# HandHeld_Terminal.net
KiCad netlist of a schematic drawn in Altium Designer
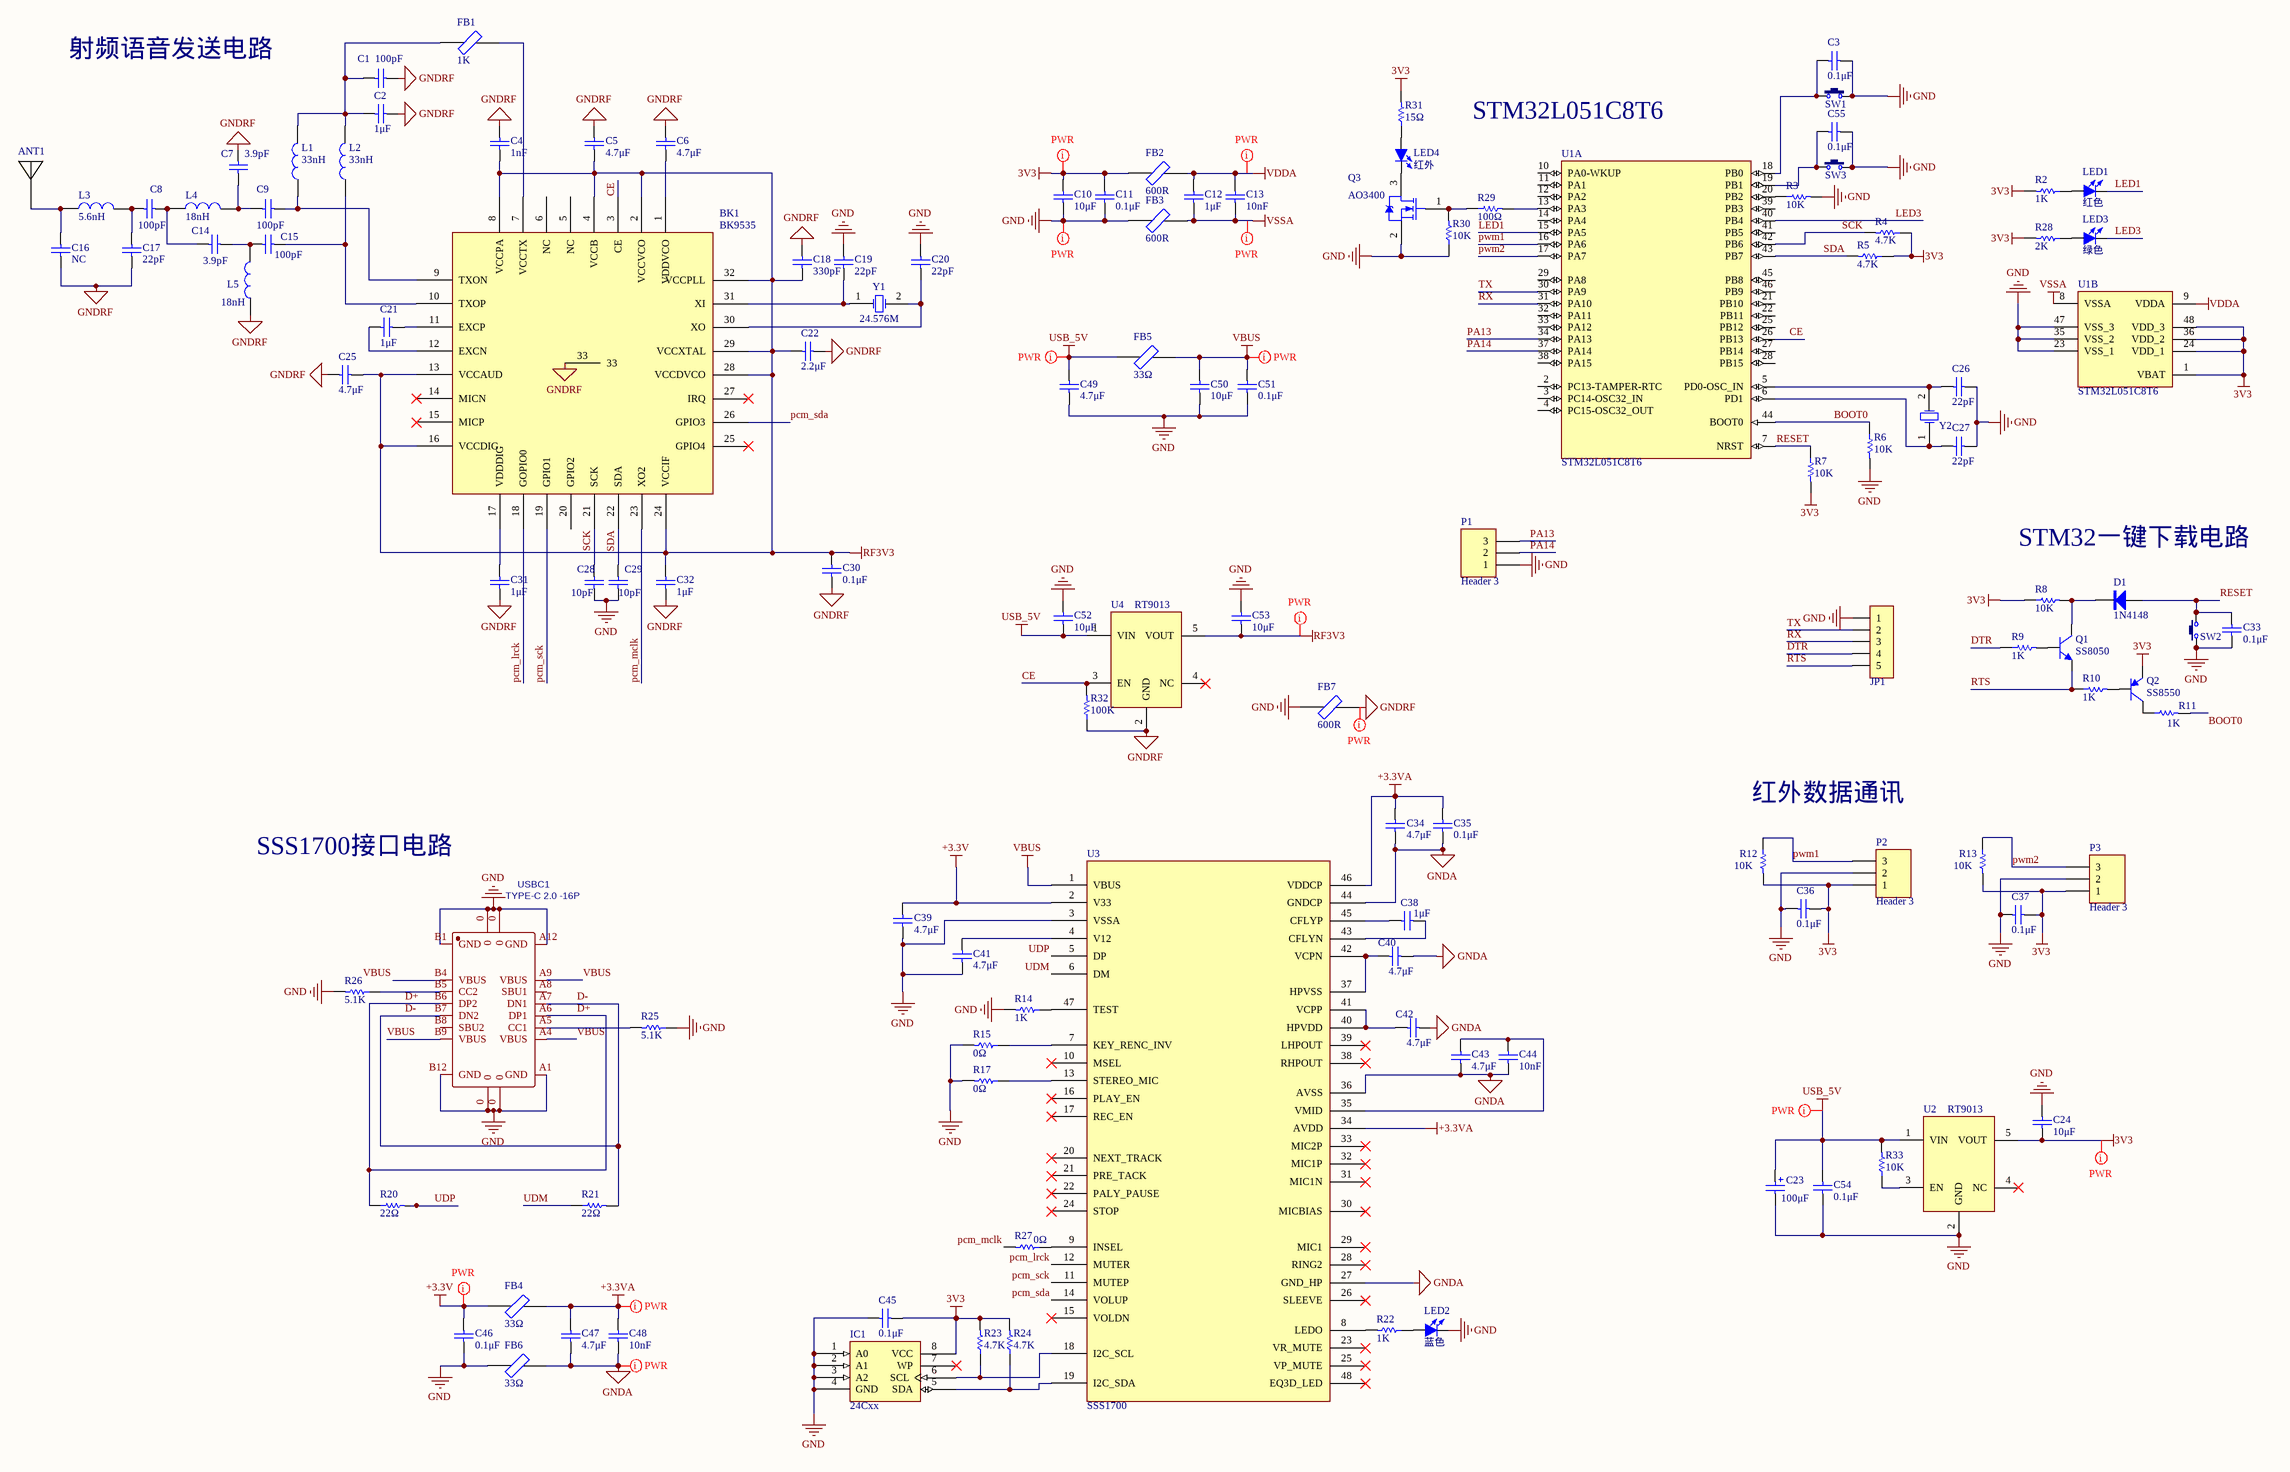
[diagram p0: HandHeld_Terminal.SchDoc]

(export (version "E")
  (design (tool "Eeschema 10.0.6"))
  (components
    (comp (ref "ANT1")
      (value "~")
      (footprint "ANT")
      (description "PCB板载天线")
      (fields (field (name "版权归属") "源创客"))
      (libsource (lib "手持发射端") (part "ANT1"))
    )
    (comp (ref "BK1") (value "BK9535") (footprint "QFN32 5x5_N") (libsource (lib "Nixie") (part "BK9530")))
    (comp (ref "C1")
      (value "100pF")
      (footprint "C 0603_L")
      (description "Capacitor")
      (fields (field (name "Comment") "Cap") (field (name "PUBLISHER") "Altium Limited"))
      (libsource (lib "Nixie") (part "Cap"))
    )
    (comp (ref "C2")
      (value "1μF")
      (footprint "C 0603_L")
      (description "Capacitor")
      (fields (field (name "Comment") "Cap") (field (name "PUBLISHER") "Altium Limited"))
      (libsource (lib "Nixie") (part "Cap"))
    )
    (comp (ref "C3")
      (value "0.1μF")
      (footprint "C 0603_L")
      (description "Capacitor")
      (fields (field (name "Comment") "Cap") (field (name "PUBLISHER") "Altium Limited"))
      (libsource (lib "Nixie") (part "Cap"))
    )
    (comp (ref "C4")
      (value "1nF")
      (footprint "C 0805_L")
      (description "Capacitor")
      (fields (field (name "Comment") "Cap") (field (name "PUBLISHER") "Altium Limited"))
      (libsource (lib "Nixie") (part "Cap"))
    )
    (comp (ref "C5")
      (value "4.7μF")
      (footprint "C 0805_L")
      (description "Capacitor")
      (fields (field (name "Comment") "Cap") (field (name "PUBLISHER") "Altium Limited"))
      (libsource (lib "Nixie") (part "Cap"))
    )
    (comp (ref "C6")
      (value "4.7μF")
      (footprint "C 0805_L")
      (description "Capacitor")
      (fields (field (name "Comment") "Cap") (field (name "PUBLISHER") "Altium Limited"))
      (libsource (lib "Nixie") (part "Cap"))
    )
    (comp (ref "C7")
      (value "3.9pF")
      (footprint "C 0603_L")
      (description "Capacitor")
      (fields (field (name "Comment") "Cap") (field (name "PUBLISHER") "Altium Limited"))
      (libsource (lib "Nixie") (part "Cap"))
    )
    (comp (ref "C8")
      (value "100pF")
      (footprint "C 0603_L")
      (description "Capacitor")
      (fields (field (name "Comment") "Cap") (field (name "PUBLISHER") "Altium Limited"))
      (libsource (lib "Nixie") (part "Cap"))
    )
    (comp (ref "C9")
      (value "100pF")
      (footprint "C 0603_L")
      (description "Capacitor")
      (fields (field (name "Comment") "Cap") (field (name "PUBLISHER") "Altium Limited"))
      (libsource (lib "Nixie") (part "Cap"))
    )
    (comp (ref "C10")
      (value "10μF")
      (footprint "C 0805_L")
      (description "Capacitor")
      (fields (field (name "Comment") "Cap") (field (name "PUBLISHER") "Altium Limited"))
      (libsource (lib "Nixie") (part "Cap"))
    )
    (comp (ref "C11")
      (value "0.1μF")
      (footprint "C 0603_L")
      (description "Capacitor")
      (fields (field (name "Comment") "Cap") (field (name "PUBLISHER") "Altium Limited"))
      (libsource (lib "Nixie") (part "Cap"))
    )
    (comp (ref "C12")
      (value "1μF")
      (footprint "C 0805_L")
      (description "Capacitor")
      (fields (field (name "Comment") "Cap") (field (name "PUBLISHER") "Altium Limited"))
      (libsource (lib "Nixie") (part "Cap"))
    )
    (comp (ref "C13")
      (value "10nF")
      (footprint "C 0805_L")
      (description "Capacitor")
      (fields (field (name "Comment") "Cap") (field (name "PUBLISHER") "Altium Limited"))
      (libsource (lib "Nixie") (part "Cap"))
    )
    (comp (ref "C14")
      (value "3.9pF")
      (footprint "C 0603_L")
      (description "Capacitor")
      (fields (field (name "Comment") "Cap") (field (name "PUBLISHER") "Altium Limited"))
      (libsource (lib "Nixie") (part "Cap"))
    )
    (comp (ref "C15")
      (value "100pF")
      (footprint "C 0603_L")
      (description "Capacitor")
      (fields (field (name "Comment") "Cap") (field (name "PUBLISHER") "Altium Limited"))
      (libsource (lib "Nixie") (part "Cap"))
    )
    (comp (ref "C16")
      (value "NC")
      (footprint "C 0603_L")
      (description "Capacitor")
      (fields (field (name "Comment") "Cap") (field (name "PUBLISHER") "Altium Limited"))
      (libsource (lib "Nixie") (part "Cap"))
    )
    (comp (ref "C17")
      (value "22pF")
      (footprint "C 0603_L")
      (description "Capacitor")
      (fields (field (name "Comment") "Cap") (field (name "PUBLISHER") "Altium Limited"))
      (libsource (lib "Nixie") (part "Cap"))
    )
    (comp (ref "C18")
      (value "330pF")
      (footprint "C 0805_L")
      (description "Capacitor")
      (fields (field (name "Comment") "Cap") (field (name "PUBLISHER") "Altium Limited"))
      (libsource (lib "Nixie") (part "Cap"))
    )
    (comp (ref "C19")
      (value "22pF")
      (footprint "C 0603_L")
      (description "Capacitor")
      (fields (field (name "Comment") "Cap") (field (name "PUBLISHER") "Altium Limited"))
      (libsource (lib "Nixie") (part "Cap"))
    )
    (comp (ref "C20")
      (value "22pF")
      (footprint "C 0603_L")
      (description "Capacitor")
      (fields (field (name "Comment") "Cap") (field (name "PUBLISHER") "Altium Limited"))
      (libsource (lib "Nixie") (part "Cap"))
    )
    (comp (ref "C21")
      (value "1μF")
      (footprint "C 0603_L")
      (description "Capacitor")
      (fields (field (name "Comment") "Cap") (field (name "PUBLISHER") "Altium Limited"))
      (libsource (lib "Nixie") (part "Cap"))
    )
    (comp (ref "C22")
      (value "2.2μF")
      (footprint "C 0805_L")
      (description "Capacitor")
      (fields (field (name "Comment") "Cap") (field (name "PUBLISHER") "Altium Limited"))
      (libsource (lib "Nixie") (part "Cap"))
    )
    (comp (ref "C23")
      (value "100μF")
      (footprint "CM C(5*5.4)")
      (description "Polarized Capacitor (Radial)")
      (fields (field (name "Comment") "Cap Pol1") (field (name "PUBLISHER") "Altium Limited"))
      (libsource (lib "Nixie") (part "Cap Pol1"))
    )
    (comp (ref "C24")
      (value "10μF")
      (footprint "C 0805_L")
      (description "Capacitor")
      (fields (field (name "Comment") "Cap") (field (name "PUBLISHER") "Altium Limited"))
      (libsource (lib "Nixie") (part "Cap"))
    )
    (comp (ref "C25")
      (value "4.7μF")
      (footprint "C 0805_L")
      (description "Capacitor")
      (fields (field (name "Comment") "Cap") (field (name "PUBLISHER") "Altium Limited"))
      (libsource (lib "Nixie") (part "Cap"))
    )
    (comp (ref "C26")
      (value "22pF")
      (footprint "C 0603_L")
      (description "Capacitor")
      (fields (field (name "Comment") "Cap") (field (name "PUBLISHER") "Altium Limited"))
      (libsource (lib "Nixie") (part "Cap"))
    )
    (comp (ref "C27")
      (value "22pF")
      (footprint "C 0603_L")
      (description "Capacitor")
      (fields (field (name "Comment") "Cap") (field (name "PUBLISHER") "Altium Limited"))
      (libsource (lib "Nixie") (part "Cap"))
    )
    (comp (ref "C28")
      (value "10pF")
      (footprint "C 0603_L")
      (description "Capacitor")
      (fields (field (name "Comment") "Cap") (field (name "PUBLISHER") "Altium Limited"))
      (libsource (lib "Nixie") (part "Cap"))
    )
    (comp (ref "C29")
      (value "10pF")
      (footprint "C 0603_L")
      (description "Capacitor")
      (fields (field (name "Comment") "Cap") (field (name "PUBLISHER") "Altium Limited"))
      (libsource (lib "Nixie") (part "Cap"))
    )
    (comp (ref "C30")
      (value "0.1μF")
      (footprint "C 0603_L")
      (description "Capacitor")
      (fields (field (name "Comment") "Cap") (field (name "PUBLISHER") "Altium Limited"))
      (libsource (lib "Nixie") (part "Cap"))
    )
    (comp (ref "C31")
      (value "1μF")
      (footprint "C 0805_L")
      (description "Capacitor")
      (fields (field (name "Comment") "Cap") (field (name "PUBLISHER") "Altium Limited"))
      (libsource (lib "Nixie") (part "Cap"))
    )
    (comp (ref "C32")
      (value "1μF")
      (footprint "C 0805_L")
      (description "Capacitor")
      (fields (field (name "Comment") "Cap") (field (name "PUBLISHER") "Altium Limited"))
      (libsource (lib "Nixie") (part "Cap"))
    )
    (comp (ref "C33")
      (value "0.1μF")
      (footprint "C 0603_L")
      (description "Capacitor")
      (fields (field (name "Comment") "Cap") (field (name "PUBLISHER") "Altium Limited"))
      (libsource (lib "Nixie") (part "Cap"))
    )
    (comp (ref "C34")
      (value "4.7μF")
      (footprint "C 0805_L")
      (description "Capacitor")
      (fields (field (name "Comment") "Cap") (field (name "PUBLISHER") "Altium Limited"))
      (libsource (lib "Nixie") (part "Cap"))
    )
    (comp (ref "C35")
      (value "0.1μF")
      (footprint "C 0603_L")
      (description "Capacitor")
      (fields (field (name "Comment") "Cap") (field (name "PUBLISHER") "Altium Limited"))
      (libsource (lib "Nixie") (part "Cap"))
    )
    (comp (ref "C36")
      (value "0.1μF")
      (footprint "C 0603_L")
      (description "Capacitor")
      (fields (field (name "Comment") "Cap") (field (name "PUBLISHER") "Altium Limited"))
      (libsource (lib "Nixie") (part "Cap"))
    )
    (comp (ref "C37")
      (value "0.1μF")
      (footprint "C 0603_L")
      (description "Capacitor")
      (fields (field (name "Comment") "Cap") (field (name "PUBLISHER") "Altium Limited"))
      (libsource (lib "Nixie") (part "Cap"))
    )
    (comp (ref "C38")
      (value "1μF")
      (footprint "C 0805_L")
      (description "Capacitor")
      (fields (field (name "Comment") "Cap") (field (name "PUBLISHER") "Altium Limited"))
      (libsource (lib "Nixie") (part "Cap"))
    )
    (comp (ref "C39")
      (value "4.7μF")
      (footprint "C 0805_L")
      (description "Capacitor")
      (fields (field (name "Comment") "Cap") (field (name "PUBLISHER") "Altium Limited"))
      (libsource (lib "Nixie") (part "Cap"))
    )
    (comp (ref "C40")
      (value "4.7μF")
      (footprint "C 0805_L")
      (description "Capacitor")
      (fields (field (name "Comment") "Cap") (field (name "PUBLISHER") "Altium Limited"))
      (libsource (lib "Nixie") (part "Cap"))
    )
    (comp (ref "C41")
      (value "4.7μF")
      (footprint "C 0805_L")
      (description "Capacitor")
      (fields (field (name "Comment") "Cap") (field (name "PUBLISHER") "Altium Limited"))
      (libsource (lib "Nixie") (part "Cap"))
    )
    (comp (ref "C42")
      (value "4.7μF")
      (footprint "C 0805_L")
      (description "Capacitor")
      (fields (field (name "Comment") "Cap") (field (name "PUBLISHER") "Altium Limited"))
      (libsource (lib "Nixie") (part "Cap"))
    )
    (comp (ref "C43")
      (value "4.7μF")
      (footprint "C 0805_L")
      (description "Capacitor")
      (fields (field (name "Comment") "Cap") (field (name "PUBLISHER") "Altium Limited"))
      (libsource (lib "Nixie") (part "Cap"))
    )
    (comp (ref "C44")
      (value "10nF")
      (footprint "C 0805_L")
      (description "Capacitor")
      (fields (field (name "Comment") "Cap") (field (name "PUBLISHER") "Altium Limited"))
      (libsource (lib "Nixie") (part "Cap"))
    )
    (comp (ref "C45")
      (value "0.1μF")
      (footprint "C 0603_L")
      (description "Capacitor")
      (fields (field (name "Comment") "Cap") (field (name "PUBLISHER") "Altium Limited"))
      (libsource (lib "Nixie") (part "Cap"))
    )
    (comp (ref "C46")
      (value "0.1μF")
      (footprint "C 0603_L")
      (description "Capacitor")
      (fields (field (name "Comment") "Cap") (field (name "PUBLISHER") "Altium Limited"))
      (libsource (lib "Nixie") (part "Cap"))
    )
    (comp (ref "C47")
      (value "4.7μF")
      (footprint "C 0805_L")
      (description "Capacitor")
      (fields (field (name "Comment") "Cap") (field (name "PUBLISHER") "Altium Limited"))
      (libsource (lib "Nixie") (part "Cap"))
    )
    (comp (ref "C48")
      (value "10nF")
      (footprint "C 0805_L")
      (description "Capacitor")
      (fields (field (name "Comment") "Cap") (field (name "PUBLISHER") "Altium Limited"))
      (libsource (lib "Nixie") (part "Cap"))
    )
    (comp (ref "C49")
      (value "4.7μF")
      (footprint "C 0805_L")
      (description "Capacitor")
      (fields (field (name "Comment") "Cap") (field (name "PUBLISHER") "Altium Limited"))
      (libsource (lib "Nixie") (part "Cap"))
    )
    (comp (ref "C50")
      (value "10μF")
      (footprint "C 0805_L")
      (description "Capacitor")
      (fields (field (name "Comment") "Cap") (field (name "PUBLISHER") "Altium Limited"))
      (libsource (lib "Nixie") (part "Cap"))
    )
    (comp (ref "C51")
      (value "0.1μF")
      (footprint "C 0603_L")
      (description "Capacitor")
      (fields (field (name "Comment") "Cap") (field (name "PUBLISHER") "Altium Limited"))
      (libsource (lib "Nixie") (part "Cap"))
    )
    (comp (ref "C52")
      (value "10μF")
      (footprint "C 0805_L")
      (description "Capacitor")
      (fields (field (name "Comment") "Cap") (field (name "PUBLISHER") "Altium Limited"))
      (libsource (lib "Nixie") (part "Cap"))
    )
    (comp (ref "C53")
      (value "10μF")
      (footprint "C 0805_L")
      (description "Capacitor")
      (fields (field (name "Comment") "Cap") (field (name "PUBLISHER") "Altium Limited"))
      (libsource (lib "Nixie") (part "Cap"))
    )
    (comp (ref "C54")
      (value "0.1μF")
      (footprint "C 0603_L")
      (description "Capacitor")
      (fields (field (name "Comment") "Cap") (field (name "PUBLISHER") "Altium Limited"))
      (libsource (lib "Nixie") (part "Cap"))
    )
    (comp (ref "C55")
      (value "0.1μF")
      (footprint "C 0603_L")
      (description "Capacitor")
      (fields (field (name "Comment") "Cap") (field (name "PUBLISHER") "Altium Limited"))
      (libsource (lib "Nixie") (part "Cap"))
    )
    (comp (ref "D1")
      (value "1N4148")
      (footprint "SOD-323")
      (description "开关二极管")
      (libsource (lib "Nixie") (part "1N4148"))
    )
    (comp (ref "FB1")
      (value "1K")
      (footprint "C 0603_L")
      (description "铁氧体磁珠")
      (fields (field (name "Comment") "Ferrite bead"))
      (libsource (lib "Nixie") (part "Ferrite bead"))
    )
    (comp (ref "FB2")
      (value "600R")
      (footprint "C 0603_L")
      (description "铁氧体磁珠")
      (fields (field (name "Comment") "Ferrite bead"))
      (libsource (lib "Nixie") (part "Ferrite bead"))
    )
    (comp (ref "FB3")
      (value "600R")
      (footprint "C 0603_L")
      (description "铁氧体磁珠")
      (fields (field (name "Comment") "Ferrite bead"))
      (libsource (lib "Nixie") (part "Ferrite bead"))
    )
    (comp (ref "FB4")
      (value "33Ω")
      (footprint "C 0603_L")
      (description "铁氧体磁珠")
      (fields (field (name "Comment") "Ferrite bead"))
      (libsource (lib "Nixie") (part "Ferrite bead"))
    )
    (comp (ref "FB5")
      (value "33Ω")
      (footprint "C 0603_L")
      (description "铁氧体磁珠")
      (fields (field (name "Comment") "Ferrite bead"))
      (libsource (lib "Nixie") (part "Ferrite bead"))
    )
    (comp (ref "FB6")
      (value "33Ω")
      (footprint "C 0603_L")
      (description "铁氧体磁珠")
      (fields (field (name "Comment") "Ferrite bead"))
      (libsource (lib "Nixie") (part "Ferrite bead"))
    )
    (comp (ref "FB7")
      (value "600R")
      (footprint "C 0603_L")
      (description "铁氧体磁珠")
      (fields (field (name "Comment") "Ferrite bead"))
      (libsource (lib "Nixie") (part "Ferrite bead"))
    )
    (comp (ref "IC1")
      (value "24Cxx")
      (footprint "SOP8_L")
      (description "外置EEPROM")
      (fields (field (name "版权归属") "封装库来自淘宝 ID：黄晶宝石"))
      (libsource (lib "Nixie") (part "24Cxx"))
    )
    (comp (ref "JP1")
      (value "HDR-1X5")
      (footprint "HDR2.0-LI-5P")
      (description "5P接插件")
      (fields (field (name "版权归属") "封装库来自淘宝 ID：黄晶宝石"))
      (libsource (lib "Nixie") (part "Header 5"))
    )
    (comp (ref "L1")
      (value "33nH")
      (footprint "L 0603")
      (description "小功率贴片电感")
      (fields (field (name "Comment") "L"))
      (libsource (lib "Nixie") (part "L"))
    )
    (comp (ref "L2")
      (value "33nH")
      (footprint "L 0603")
      (description "小功率贴片电感")
      (fields (field (name "Comment") "L"))
      (libsource (lib "Nixie") (part "L"))
    )
    (comp (ref "L3")
      (value "5.6nH")
      (footprint "L 0603")
      (description "小功率贴片电感")
      (fields (field (name "Comment") "L"))
      (libsource (lib "Nixie") (part "L"))
    )
    (comp (ref "L4")
      (value "18nH")
      (footprint "L 0603")
      (description "小功率贴片电感")
      (fields (field (name "Comment") "L"))
      (libsource (lib "Nixie") (part "L"))
    )
    (comp (ref "L5")
      (value "18nH")
      (footprint "L 0603")
      (description "小功率贴片电感")
      (fields (field (name "Comment") "L"))
      (libsource (lib "Nixie") (part "L"))
    )
    (comp (ref "LED1")
      (value "红色")
      (footprint "LED 0805R")
      (description "贴片LED")
      (fields (field (name "版权归属") "封装库来自淘宝 ID：黄晶宝石"))
      (libsource (lib "Nixie") (part "LED-SMD"))
    )
    (comp (ref "LED2")
      (value "蓝色")
      (footprint "LED 0805B")
      (description "贴片LED")
      (fields (field (name "版权归属") "封装库来自淘宝 ID：黄晶宝石"))
      (libsource (lib "Nixie") (part "LED-SMD"))
    )
    (comp (ref "LED3")
      (value "绿色")
      (footprint "LED 0805G")
      (description "贴片LED")
      (fields (field (name "版权归属") "封装库来自淘宝 ID：黄晶宝石"))
      (libsource (lib "Nixie") (part "LED-SMD"))
    )
    (comp (ref "LED4")
      (value "红外")
      (footprint "LED 3MM-R")
      (description "贴片LED")
      (fields (field (name "版权归属") "封装库来自淘宝 ID：黄晶宝石"))
      (libsource (lib "Nixie") (part "LED-SMD"))
    )
    (comp (ref "P1")
      (value "Header 3")
      (footprint "HDR1X3")
      (description "Header, 3-Pin")
      (fields (field (name "PUBLISHER") "Altium Limited"))
      (libsource (lib "") (part "Header 3_1"))
    )
    (comp (ref "P2")
      (value "Header 3")
      (footprint "HDR1X3")
      (description "Header, 3-Pin")
      (fields (field (name "PUBLISHER") "Altium Limited"))
      (libsource (lib "Miscellaneous Connectors") (part "Header 3"))
    )
    (comp (ref "P3")
      (value "Header 3")
      (footprint "HDR1X3")
      (description "Header, 3-Pin")
      (fields (field (name "PUBLISHER") "Altium Limited"))
      (libsource (lib "Miscellaneous Connectors") (part "Header 3"))
    )
    (comp (ref "Q1")
      (value "SS8050")
      (footprint "SOT-23-3L")
      (description "高频放大-NPN型")
      (fields (field (name "版权归属") "封装库来自淘宝 ID：黄晶宝石"))
      (libsource (lib "Nixie") (part "8050-SMD"))
    )
    (comp (ref "Q2")
      (value "SS8550")
      (footprint "SOT-23-3L")
      (description "高频放大-PNP型")
      (fields (field (name "版权归属") "封装库来自淘宝 ID：黄晶宝石"))
      (libsource (lib "Nixie") (part "8550-SMD"))
    )
    (comp (ref "Q3")
      (value "AO3400")
      (footprint "SOT-23-3L")
      (description "N-Channel Power MOSFET")
      (fields (field (name "PUBLISHER") "Altium Limited"))
      (libsource (lib "Nixie") (part "NMOS-2"))
    )
    (comp (ref "R2")
      (value "1K")
      (footprint "R 0805_L")
      (description "Resistor")
      (fields (field (name "PUBLISHER") "Altium Limited"))
      (libsource (lib "Nixie") (part "Resistor"))
    )
    (comp (ref "R3")
      (value "10K")
      (footprint "R 0805_L")
      (description "Resistor")
      (fields (field (name "PUBLISHER") "Altium Limited"))
      (libsource (lib "Nixie") (part "Resistor"))
    )
    (comp (ref "R4")
      (value "4.7K")
      (footprint "R 0603_L")
      (description "Resistor")
      (fields (field (name "PUBLISHER") "Altium Limited"))
      (libsource (lib "Nixie") (part "Resistor"))
    )
    (comp (ref "R5")
      (value "4.7K")
      (footprint "R 0603_L")
      (description "Resistor")
      (fields (field (name "PUBLISHER") "Altium Limited"))
      (libsource (lib "Nixie") (part "Resistor"))
    )
    (comp (ref "R6")
      (value "10K")
      (footprint "R 0805_L")
      (description "Resistor")
      (fields (field (name "PUBLISHER") "Altium Limited"))
      (libsource (lib "Nixie") (part "Resistor"))
    )
    (comp (ref "R7")
      (value "10K")
      (footprint "R 0805_L")
      (description "Resistor")
      (fields (field (name "PUBLISHER") "Altium Limited"))
      (libsource (lib "Nixie") (part "Resistor"))
    )
    (comp (ref "R8")
      (value "10K")
      (footprint "R 0805_L")
      (description "Resistor")
      (fields (field (name "PUBLISHER") "Altium Limited"))
      (libsource (lib "Nixie") (part "Resistor"))
    )
    (comp (ref "R9")
      (value "1K")
      (footprint "R 0805_L")
      (description "Resistor")
      (fields (field (name "PUBLISHER") "Altium Limited"))
      (libsource (lib "Nixie") (part "Resistor"))
    )
    (comp (ref "R10")
      (value "1K")
      (footprint "R 0805_L")
      (description "Resistor")
      (fields (field (name "PUBLISHER") "Altium Limited"))
      (libsource (lib "Nixie") (part "Resistor"))
    )
    (comp (ref "R11")
      (value "1K")
      (footprint "R 0805_L")
      (description "Resistor")
      (fields (field (name "PUBLISHER") "Altium Limited"))
      (libsource (lib "Nixie") (part "Resistor"))
    )
    (comp (ref "R12")
      (value "10K")
      (footprint "R 0805_L")
      (description "Resistor")
      (fields (field (name "PUBLISHER") "Altium Limited"))
      (libsource (lib "Nixie") (part "Resistor"))
    )
    (comp (ref "R13")
      (value "10K")
      (footprint "R 0805_L")
      (description "Resistor")
      (fields (field (name "PUBLISHER") "Altium Limited"))
      (libsource (lib "Nixie") (part "Resistor"))
    )
    (comp (ref "R14")
      (value "1K")
      (footprint "R 0805_L")
      (description "Resistor")
      (fields (field (name "PUBLISHER") "Altium Limited"))
      (libsource (lib "Nixie") (part "Resistor"))
    )
    (comp (ref "R15")
      (value "0Ω")
      (footprint "R 0603_L")
      (description "Resistor")
      (fields (field (name "PUBLISHER") "Altium Limited"))
      (libsource (lib "Nixie") (part "Resistor"))
    )
    (comp (ref "R17")
      (value "0Ω")
      (footprint "R 0603_L")
      (description "Resistor")
      (fields (field (name "PUBLISHER") "Altium Limited"))
      (libsource (lib "Nixie") (part "Resistor"))
    )
    (comp (ref "R20")
      (value "22Ω")
      (footprint "R 0603_L")
      (description "Resistor")
      (fields (field (name "PUBLISHER") "Altium Limited"))
      (libsource (lib "Nixie") (part "Resistor"))
    )
    (comp (ref "R21")
      (value "22Ω")
      (footprint "R 0603_L")
      (description "Resistor")
      (fields (field (name "PUBLISHER") "Altium Limited"))
      (libsource (lib "Nixie") (part "Resistor"))
    )
    (comp (ref "R22")
      (value "1K")
      (footprint "R 0805_L")
      (description "Resistor")
      (fields (field (name "PUBLISHER") "Altium Limited"))
      (libsource (lib "Nixie") (part "Resistor"))
    )
    (comp (ref "R23")
      (value "4.7K")
      (footprint "R 0603_L")
      (description "Resistor")
      (fields (field (name "PUBLISHER") "Altium Limited"))
      (libsource (lib "Nixie") (part "Resistor"))
    )
    (comp (ref "R24")
      (value "4.7K")
      (footprint "R 0603_L")
      (description "Resistor")
      (fields (field (name "PUBLISHER") "Altium Limited"))
      (libsource (lib "Nixie") (part "Resistor"))
    )
    (comp (ref "R25")
      (value "5.1K")
      (footprint "R 0603_L")
      (description "Resistor")
      (fields (field (name "PUBLISHER") "Altium Limited"))
      (libsource (lib "Nixie") (part "Resistor"))
    )
    (comp (ref "R26")
      (value "5.1K")
      (footprint "R 0603_L")
      (description "Resistor")
      (fields (field (name "PUBLISHER") "Altium Limited"))
      (libsource (lib "Nixie") (part "Resistor"))
    )
    (comp (ref "R27")
      (value "0Ω")
      (footprint "R 0603_L")
      (description "Resistor")
      (fields (field (name "PUBLISHER") "Altium Limited"))
      (libsource (lib "Nixie") (part "Resistor"))
    )
    (comp (ref "R28")
      (value "2K")
      (footprint "R 0805_L")
      (description "Resistor")
      (fields (field (name "PUBLISHER") "Altium Limited"))
      (libsource (lib "Nixie") (part "Resistor"))
    )
    (comp (ref "R29")
      (value "100Ω")
      (footprint "R 0805_L")
      (description "Resistor")
      (fields (field (name "PUBLISHER") "Altium Limited"))
      (libsource (lib "Nixie") (part "Resistor"))
    )
    (comp (ref "R30")
      (value "10K")
      (footprint "R 0805_L")
      (description "Resistor")
      (fields (field (name "PUBLISHER") "Altium Limited"))
      (libsource (lib "Nixie") (part "Resistor"))
    )
    (comp (ref "R31")
      (value "15Ω")
      (footprint "R 1206_L")
      (description "Resistor")
      (fields (field (name "PUBLISHER") "Altium Limited"))
      (libsource (lib "Nixie") (part "Resistor"))
    )
    (comp (ref "R32")
      (value "100K")
      (footprint "R 0805_L")
      (description "Resistor")
      (fields (field (name "PUBLISHER") "Altium Limited"))
      (libsource (lib "Nixie") (part "Resistor"))
    )
    (comp (ref "R33")
      (value "10K")
      (footprint "R 0805_L")
      (description "Resistor")
      (fields (field (name "PUBLISHER") "Altium Limited"))
      (libsource (lib "Nixie") (part "Resistor"))
    )
    (comp (ref "SW1")
      (value "3x6x5")
      (footprint "TSW SMD-3*6*2.5")
      (description "3x6轻触开关")
      (fields (field (name "版权归属") "封装库来自淘宝 ID：黄晶宝石"))
      (libsource (lib "Nixie") (part "TSW 3x6"))
    )
    (comp (ref "SW2")
      (value "3x6x5")
      (footprint "TSW SMD-3*6*2.5")
      (description "3x6轻触开关")
      (fields (field (name "版权归属") "封装库来自淘宝 ID：黄晶宝石"))
      (libsource (lib "") (part "TSW 3x6_1"))
    )
    (comp (ref "SW3")
      (value "3x6x5")
      (footprint "TSW SMD-3*6*2.5")
      (description "3x6轻触开关")
      (fields (field (name "版权归属") "封装库来自淘宝 ID：黄晶宝石"))
      (libsource (lib "Nixie") (part "TSW 3x6"))
    )
    (comp (ref "U1")
      (value "STM32L051C8T6")
      (footprint "LQFP48_L")
      (description "ARM")
      (libsource (lib "") (part "STM32F103C8T6_1"))
    )
    (comp (ref "U2")
      (value "RT9013")
      (footprint "SOT23-5L")
      (description "LDO")
      (libsource (lib "HandHeld_terminal") (part "RT9013"))
    )
    (comp (ref "U3")
      (value "SSS1700")
      (footprint "LQFP48_L")
      (description "USB音频芯片")
      (libsource (lib "Nixie") (part "SSS1700"))
    )
    (comp (ref "U4")
      (value "RT9013")
      (footprint "SOT23-5L")
      (description "LDO")
      (libsource (lib "HandHeld_terminal") (part "RT9013"))
    )
    (comp (ref "USBC1")
      (value "TYPE-C 2.0 -16P")
      (footprint "USB-C-SMD_TYPE-C-USB-5")
      (description "USB2.0 Type-C 母座 16Pin")
      (libsource (lib "Nixie") (part "USB2.0 Type-C 16Pin母座"))
    )
    (comp (ref "Y1")
      (value "24.576M")
      (footprint "OSC 5032-2P")
      (description "Crystal Oscillator")
      (fields (field (name "PUBLISHER") "Altium Limited"))
      (libsource (lib "Miscellaneous Devices") (part "XTAL"))
    )
    (comp (ref "Y2")
      (value "8MHz ±20ppm 20pF")
      (footprint "OSC 5032-2P")
      (description "贴片晶振")
      (libsource (lib "HandHeld_terminal") (part "SMD-5032_2P 8MHz 20ppm 20pF"))
    )
  )
  (nets
    (net (code "1") (name "+3.3V") (class "Default")
      (node (ref "C39") (pin "2") (pinfunction "2_2") (pintype "passive"))
      (node (ref "C46") (pin "2") (pinfunction "2_2") (pintype "passive"))
      (node (ref "FB4") (pin "1") (pinfunction "1_1") (pintype "passive"))
      (node (ref "U3") (pin "2") (pinfunction "V33_2") (pintype "passive"))
    )
    (net (code "2") (name "+3.3VA") (class "Default")
      (node (ref "C34") (pin "2") (pinfunction "2_2") (pintype "passive"))
      (node (ref "C35") (pin "2") (pinfunction "2_2") (pintype "passive"))
      (node (ref "C47") (pin "2") (pinfunction "2_2") (pintype "passive"))
      (node (ref "C48") (pin "2") (pinfunction "2_2") (pintype "passive"))
      (node (ref "FB4") (pin "2") (pinfunction "2_2") (pintype "passive"))
      (node (ref "U3") (pin "34") (pinfunction "AVDD_34") (pintype "passive"))
      (node (ref "U3") (pin "46") (pinfunction "VDDCP_46") (pintype "passive"))
    )
    (net (code "3") (name "/BOOT0") (class "Default")
      (node (ref "R11") (pin "2") (pinfunction "2_2") (pintype "passive"))
      (node (ref "R6") (pin "1") (pinfunction "1_1") (pintype "passive"))
      (node (ref "U1") (pin "44") (pinfunction "BOOT0_44") (pintype "input"))
    )
    (net (code "4") (name "/CE") (class "Default")
      (node (ref "BK1") (pin "3") (pinfunction "CE_3") (pintype "passive"))
      (node (ref "R32") (pin "2") (pinfunction "2_2") (pintype "passive"))
      (node (ref "U1") (pin "26") (pinfunction "PB13_26") (pintype "bidirectional"))
      (node (ref "U4") (pin "3") (pinfunction "EN_3") (pintype "passive"))
    )
    (net (code "5") (name "/D+") (class "Default")
      (node (ref "R20") (pin "1") (pinfunction "1_1") (pintype "passive"))
      (node (ref "USBC1") (pin "A6") (pinfunction "DP1_A6") (pintype "passive"))
      (node (ref "USBC1") (pin "B6") (pinfunction "DP2_B6") (pintype "passive"))
    )
    (net (code "6") (name "/D-") (class "Default")
      (node (ref "R21") (pin "2") (pinfunction "2_2") (pintype "passive"))
      (node (ref "USBC1") (pin "A7") (pinfunction "DN1_A7") (pintype "passive"))
      (node (ref "USBC1") (pin "B7") (pinfunction "DN2_B7") (pintype "passive"))
    )
    (net (code "7") (name "/DTR") (class "Default")
      (node (ref "JP1") (pin "4") (pinfunction "4_4") (pintype "passive"))
      (node (ref "R9") (pin "1") (pinfunction "1_1") (pintype "passive"))
    )
    (net (code "8") (name "/LED1") (class "Default")
      (node (ref "LED1") (pin "2") (pinfunction "K_2") (pintype "passive"))
      (node (ref "U1") (pin "15") (pinfunction "PA5_15") (pintype "bidirectional"))
    )
    (net (code "9") (name "/LED3") (class "Default")
      (node (ref "LED3") (pin "2") (pinfunction "K_2") (pintype "passive"))
      (node (ref "U1") (pin "40") (pinfunction "PB4_40") (pintype "bidirectional"))
    )
    (net (code "10") (name "/PA13") (class "Default")
      (node (ref "P1") (pin "3") (pinfunction "3_3") (pintype "passive"))
      (node (ref "U1") (pin "34") (pinfunction "PA13_34") (pintype "bidirectional"))
    )
    (net (code "11") (name "/PA14") (class "Default")
      (node (ref "P1") (pin "2") (pinfunction "2_2") (pintype "passive"))
      (node (ref "U1") (pin "37") (pinfunction "PA14_37") (pintype "bidirectional"))
    )
    (net (code "12") (name "/RESET") (class "Default")
      (node (ref "C33") (pin "2") (pinfunction "2_2") (pintype "passive"))
      (node (ref "D1") (pin "1") (pinfunction "A_1") (pintype "passive"))
      (node (ref "R7") (pin "1") (pinfunction "1_1") (pintype "passive"))
      (node (ref "SW2") (pin "2") (pinfunction "2_2") (pintype "passive"))
      (node (ref "U1") (pin "7") (pinfunction "NRST_7") (pintype "bidirectional"))
    )
    (net (code "13") (name "/RTS") (class "Default")
      (node (ref "JP1") (pin "5") (pinfunction "5_5") (pintype "passive"))
      (node (ref "Q1") (pin "2") (pinfunction "E_2") (pintype "passive"))
      (node (ref "R10") (pin "1") (pinfunction "1_1") (pintype "passive"))
    )
    (net (code "14") (name "/RX") (class "Default")
      (node (ref "JP1") (pin "3") (pinfunction "3_3") (pintype "passive"))
      (node (ref "U1") (pin "31") (pinfunction "PA10_31") (pintype "bidirectional"))
    )
    (net (code "15") (name "/SCK") (class "Default")
      (node (ref "BK1") (pin "21") (pinfunction "SCK_21") (pintype "passive"))
      (node (ref "C28") (pin "2") (pinfunction "2_2") (pintype "passive"))
      (node (ref "R4") (pin "2") (pinfunction "2_2") (pintype "passive"))
      (node (ref "U1") (pin "42") (pinfunction "PB6_42") (pintype "bidirectional"))
    )
    (net (code "16") (name "/SDA") (class "Default")
      (node (ref "BK1") (pin "22") (pinfunction "SDA_22") (pintype "passive"))
      (node (ref "C29") (pin "2") (pinfunction "2_2") (pintype "passive"))
      (node (ref "R5") (pin "2") (pinfunction "2_2") (pintype "passive"))
      (node (ref "U1") (pin "43") (pinfunction "PB7_43") (pintype "bidirectional"))
    )
    (net (code "17") (name "/TX") (class "Default")
      (node (ref "JP1") (pin "2") (pinfunction "2_2") (pintype "passive"))
      (node (ref "U1") (pin "30") (pinfunction "PA9_30") (pintype "bidirectional"))
    )
    (net (code "18") (name "/UDM") (class "Default")
      (node (ref "R21") (pin "1") (pinfunction "1_1") (pintype "passive"))
      (node (ref "U3") (pin "6") (pinfunction "DM_6") (pintype "passive"))
    )
    (net (code "19") (name "/UDP") (class "Default")
      (node (ref "R20") (pin "2") (pinfunction "2_2") (pintype "passive"))
      (node (ref "U3") (pin "5") (pinfunction "DP_5") (pintype "passive"))
    )
    (net (code "20") (name "/pcm_lrck") (class "Default")
      (node (ref "BK1") (pin "18") (pinfunction "GOPIO0_18") (pintype "passive"))
      (node (ref "U3") (pin "12") (pinfunction "MUTER_12") (pintype "passive"))
    )
    (net (code "21") (name "/pcm_mclk") (class "Default")
      (node (ref "BK1") (pin "23") (pinfunction "XO2_23") (pintype "passive"))
      (node (ref "R27") (pin "2") (pinfunction "2_2") (pintype "passive"))
    )
    (net (code "22") (name "/pcm_sck") (class "Default")
      (node (ref "BK1") (pin "19") (pinfunction "GPIO1_19") (pintype "passive"))
      (node (ref "U3") (pin "11") (pinfunction "MUTEP_11") (pintype "passive"))
    )
    (net (code "23") (name "/pcm_sda") (class "Default")
      (node (ref "BK1") (pin "26") (pinfunction "GPIO3_26") (pintype "passive"))
      (node (ref "U3") (pin "14") (pinfunction "VOLUP_14") (pintype "passive"))
    )
    (net (code "24") (name "/pwm1") (class "Default")
      (node (ref "P2") (pin "3") (pinfunction "3_3") (pintype "passive"))
      (node (ref "R12") (pin "1") (pinfunction "1_1") (pintype "passive"))
      (node (ref "U1") (pin "16") (pinfunction "PA6_16") (pintype "bidirectional"))
    )
    (net (code "25") (name "/pwm2") (class "Default")
      (node (ref "P3") (pin "3") (pinfunction "3_3") (pintype "passive"))
      (node (ref "R13") (pin "1") (pinfunction "1_1") (pintype "passive"))
      (node (ref "U1") (pin "17") (pinfunction "PA7_17") (pintype "bidirectional"))
    )
    (net (code "26") (name "3V3") (class "Default")
      (node (ref "C10") (pin "2") (pinfunction "2_2") (pintype "passive"))
      (node (ref "C11") (pin "2") (pinfunction "2_2") (pintype "passive"))
      (node (ref "C24") (pin "1") (pinfunction "1_1") (pintype "passive"))
      (node (ref "C36") (pin "1") (pinfunction "1_1") (pintype "passive"))
      (node (ref "C37") (pin "1") (pinfunction "1_1") (pintype "passive"))
      (node (ref "C45") (pin "1") (pinfunction "1_1") (pintype "passive"))
      (node (ref "FB2") (pin "1") (pinfunction "1_1") (pintype "passive"))
      (node (ref "IC1") (pin "8") (pinfunction "VCC_8") (pintype "power_in"))
      (node (ref "P2") (pin "1") (pinfunction "1_1") (pintype "passive"))
      (node (ref "P3") (pin "1") (pinfunction "1_1") (pintype "passive"))
      (node (ref "Q2") (pin "2") (pinfunction "E_2") (pintype "passive"))
      (node (ref "R12") (pin "2") (pinfunction "2_2") (pintype "passive"))
      (node (ref "R13") (pin "2") (pinfunction "2_2") (pintype "passive"))
      (node (ref "R2") (pin "2") (pinfunction "2_2") (pintype "passive"))
      (node (ref "R23") (pin "2") (pinfunction "2_2") (pintype "passive"))
      (node (ref "R24") (pin "2") (pinfunction "2_2") (pintype "passive"))
      (node (ref "R28") (pin "2") (pinfunction "2_2") (pintype "passive"))
      (node (ref "R31") (pin "2") (pinfunction "2_2") (pintype "passive"))
      (node (ref "R4") (pin "1") (pinfunction "1_1") (pintype "passive"))
      (node (ref "R5") (pin "1") (pinfunction "1_1") (pintype "passive"))
      (node (ref "R7") (pin "2") (pinfunction "2_2") (pintype "passive"))
      (node (ref "R8") (pin "1") (pinfunction "1_1") (pintype "passive"))
      (node (ref "U1") (pin "1") (pinfunction "VBAT_1") (pintype "power_in"))
      (node (ref "U1") (pin "24") (pinfunction "VDD_1_24") (pintype "power_in"))
      (node (ref "U1") (pin "36") (pinfunction "VDD_2_36") (pintype "power_in"))
      (node (ref "U1") (pin "48") (pinfunction "VDD_3_48") (pintype "power_in"))
      (node (ref "U2") (pin "5") (pinfunction "VOUT_5") (pintype "passive"))
    )
    (net (code "27") (name "GND") (class "Default")
      (node (ref "C10") (pin "1") (pinfunction "1_1") (pintype "passive"))
      (node (ref "C11") (pin "1") (pinfunction "1_1") (pintype "passive"))
      (node (ref "C19") (pin "2") (pinfunction "2_2") (pintype "passive"))
      (node (ref "C20") (pin "2") (pinfunction "2_2") (pintype "passive"))
      (node (ref "C23") (pin "2") (pinfunction "2_2") (pintype "passive"))
      (node (ref "C24") (pin "2") (pinfunction "2_2") (pintype "passive"))
      (node (ref "C26") (pin "1") (pinfunction "1_1") (pintype "passive"))
      (node (ref "C27") (pin "1") (pinfunction "1_1") (pintype "passive"))
      (node (ref "C28") (pin "1") (pinfunction "1_1") (pintype "passive"))
      (node (ref "C29") (pin "1") (pinfunction "1_1") (pintype "passive"))
      (node (ref "C3") (pin "1") (pinfunction "1_1") (pintype "passive"))
      (node (ref "C33") (pin "1") (pinfunction "1_1") (pintype "passive"))
      (node (ref "C36") (pin "2") (pinfunction "2_2") (pintype "passive"))
      (node (ref "C37") (pin "2") (pinfunction "2_2") (pintype "passive"))
      (node (ref "C39") (pin "1") (pinfunction "1_1") (pintype "passive"))
      (node (ref "C41") (pin "1") (pinfunction "1_1") (pintype "passive"))
      (node (ref "C45") (pin "2") (pinfunction "2_2") (pintype "passive"))
      (node (ref "C46") (pin "1") (pinfunction "1_1") (pintype "passive"))
      (node (ref "C49") (pin "1") (pinfunction "1_1") (pintype "passive"))
      (node (ref "C50") (pin "1") (pinfunction "1_1") (pintype "passive"))
      (node (ref "C51") (pin "1") (pinfunction "1_1") (pintype "passive"))
      (node (ref "C52") (pin "2") (pinfunction "2_2") (pintype "passive"))
      (node (ref "C53") (pin "2") (pinfunction "2_2") (pintype "passive"))
      (node (ref "C54") (pin "2") (pinfunction "2_2") (pintype "passive"))
      (node (ref "C55") (pin "1") (pinfunction "1_1") (pintype "passive"))
      (node (ref "FB3") (pin "1") (pinfunction "1_1") (pintype "passive"))
      (node (ref "FB6") (pin "1") (pinfunction "1_1") (pintype "passive"))
      (node (ref "FB7") (pin "1") (pinfunction "1_1") (pintype "passive"))
      (node (ref "IC1") (pin "1") (pinfunction "A0_1") (pintype "input"))
      (node (ref "IC1") (pin "2") (pinfunction "A1_2") (pintype "input"))
      (node (ref "IC1") (pin "3") (pinfunction "A2_3") (pintype "input"))
      (node (ref "IC1") (pin "4") (pinfunction "GND_4") (pintype "passive"))
      (node (ref "JP1") (pin "1") (pinfunction "1_1") (pintype "passive"))
      (node (ref "LED2") (pin "2") (pinfunction "K_2") (pintype "passive"))
      (node (ref "P1") (pin "1") (pinfunction "1_1") (pintype "passive"))
      (node (ref "P2") (pin "2") (pinfunction "2_2") (pintype "passive"))
      (node (ref "P3") (pin "2") (pinfunction "2_2") (pintype "passive"))
      (node (ref "Q3") (pin "2") (pinfunction "S_2") (pintype "passive"))
      (node (ref "R14") (pin "2") (pinfunction "2_2") (pintype "passive"))
      (node (ref "R15") (pin "2") (pinfunction "2_2") (pintype "passive"))
      (node (ref "R17") (pin "2") (pinfunction "2_2") (pintype "passive"))
      (node (ref "R25") (pin "1") (pinfunction "1_1") (pintype "passive"))
      (node (ref "R26") (pin "2") (pinfunction "2_2") (pintype "passive"))
      (node (ref "R3") (pin "2") (pinfunction "2_2") (pintype "passive"))
      (node (ref "R30") (pin "1") (pinfunction "1_1") (pintype "passive"))
      (node (ref "R6") (pin "2") (pinfunction "2_2") (pintype "passive"))
      (node (ref "SW1") (pin "2") (pinfunction "2_2") (pintype "passive"))
      (node (ref "SW2") (pin "1") (pinfunction "1_1") (pintype "passive"))
      (node (ref "SW3") (pin "2") (pinfunction "2_2") (pintype "passive"))
      (node (ref "U1") (pin "23") (pinfunction "VSS_1_23") (pintype "power_in"))
      (node (ref "U1") (pin "35") (pinfunction "VSS_2_35") (pintype "power_in"))
      (node (ref "U1") (pin "47") (pinfunction "VSS_3_47") (pintype "power_in"))
      (node (ref "U2") (pin "2") (pinfunction "GND_2") (pintype "passive"))
      (node (ref "U3") (pin "3") (pinfunction "VSSA_3") (pintype "passive"))
      (node (ref "USBC1") (pin "0") (pinfunction "0_0") (pintype "passive"))
      (node (ref "USBC1") (pin "A1") (pinfunction "GND_A1") (pintype "passive"))
      (node (ref "USBC1") (pin "A12") (pinfunction "GND_A12") (pintype "passive"))
      (node (ref "USBC1") (pin "B1") (pinfunction "GND_B1") (pintype "passive"))
      (node (ref "USBC1") (pin "B12") (pinfunction "GND_B12") (pintype "passive"))
    )
    (net (code "28") (name "GNDA") (class "Default")
      (node (ref "C34") (pin "1") (pinfunction "1_1") (pintype "passive"))
      (node (ref "C35") (pin "1") (pinfunction "1_1") (pintype "passive"))
      (node (ref "C40") (pin "1") (pinfunction "1_1") (pintype "passive"))
      (node (ref "C42") (pin "1") (pinfunction "1_1") (pintype "passive"))
      (node (ref "C43") (pin "1") (pinfunction "1_1") (pintype "passive"))
      (node (ref "C44") (pin "1") (pinfunction "1_1") (pintype "passive"))
      (node (ref "C47") (pin "1") (pinfunction "1_1") (pintype "passive"))
      (node (ref "C48") (pin "1") (pinfunction "1_1") (pintype "passive"))
      (node (ref "FB6") (pin "2") (pinfunction "2_2") (pintype "passive"))
      (node (ref "U3") (pin "27") (pinfunction "GND_HP_27") (pintype "passive"))
      (node (ref "U3") (pin "36") (pinfunction "AVSS_36") (pintype "passive"))
      (node (ref "U3") (pin "44") (pinfunction "GNDCP_44") (pintype "passive"))
    )
    (net (code "29") (name "GNDRF") (class "Default")
      (node (ref "BK1") (pin "33") (pinfunction "33_33") (pintype "passive"))
      (node (ref "C1") (pin "1") (pinfunction "1_1") (pintype "passive"))
      (node (ref "C16") (pin "2") (pinfunction "2_2") (pintype "passive"))
      (node (ref "C17") (pin "2") (pinfunction "2_2") (pintype "passive"))
      (node (ref "C18") (pin "2") (pinfunction "2_2") (pintype "passive"))
      (node (ref "C2") (pin "1") (pinfunction "1_1") (pintype "passive"))
      (node (ref "C22") (pin "1") (pinfunction "1_1") (pintype "passive"))
      (node (ref "C25") (pin "2") (pinfunction "2_2") (pintype "passive"))
      (node (ref "C30") (pin "1") (pinfunction "1_1") (pintype "passive"))
      (node (ref "C31") (pin "1") (pinfunction "1_1") (pintype "passive"))
      (node (ref "C32") (pin "1") (pinfunction "1_1") (pintype "passive"))
      (node (ref "C4") (pin "1") (pinfunction "1_1") (pintype "passive"))
      (node (ref "C5") (pin "1") (pinfunction "1_1") (pintype "passive"))
      (node (ref "C6") (pin "1") (pinfunction "1_1") (pintype "passive"))
      (node (ref "C7") (pin "1") (pinfunction "1_1") (pintype "passive"))
      (node (ref "FB7") (pin "2") (pinfunction "2_2") (pintype "passive"))
      (node (ref "L5") (pin "1") (pinfunction "1_1") (pintype "passive"))
      (node (ref "R32") (pin "1") (pinfunction "1_1") (pintype "passive"))
      (node (ref "U4") (pin "2") (pinfunction "GND_2") (pintype "passive"))
    )
    (net (code "30") (name "Net-(ANT1-Pad1)") (class "Default")
      (node (ref "ANT1") (pin "1") (pinfunction "1_1") (pintype "passive"))
      (node (ref "C16") (pin "1") (pinfunction "1_1") (pintype "passive"))
      (node (ref "L3") (pin "1") (pinfunction "1_1") (pintype "passive"))
    )
    (net (code "31") (name "Net-(BK1-EXCN)") (class "Default")
      (node (ref "BK1") (pin "12") (pinfunction "EXCN_12") (pintype "passive"))
      (node (ref "C21") (pin "2") (pinfunction "2_2") (pintype "passive"))
    )
    (net (code "32") (name "Net-(BK1-EXCP)") (class "Default")
      (node (ref "BK1") (pin "11") (pinfunction "EXCP_11") (pintype "passive"))
      (node (ref "C21") (pin "1") (pinfunction "1_1") (pintype "passive"))
    )
    (net (code "33") (name "Net-(BK1-TXON)") (class "Default")
      (node (ref "BK1") (pin "9") (pinfunction "TXON_9") (pintype "passive"))
      (node (ref "C9") (pin "1") (pinfunction "1_1") (pintype "passive"))
      (node (ref "L1") (pin "1") (pinfunction "1_1") (pintype "passive"))
    )
    (net (code "34") (name "Net-(BK1-TXOP)") (class "Default")
      (node (ref "BK1") (pin "10") (pinfunction "TXOP_10") (pintype "passive"))
      (node (ref "C15") (pin "1") (pinfunction "1_1") (pintype "passive"))
      (node (ref "L2") (pin "1") (pinfunction "1_1") (pintype "passive"))
    )
    (net (code "35") (name "Net-(BK1-VCCTX)") (class "Default")
      (node (ref "BK1") (pin "7") (pinfunction "VCCTX_7") (pintype "passive"))
      (node (ref "FB1") (pin "2") (pinfunction "2_2") (pintype "passive"))
    )
    (net (code "36") (name "Net-(BK1-VDDDIG)") (class "Default")
      (node (ref "BK1") (pin "17") (pinfunction "VDDDIG_17") (pintype "passive"))
      (node (ref "C31") (pin "2") (pinfunction "2_2") (pintype "passive"))
    )
    (net (code "37") (name "Net-(BK1-VDDVCO)") (class "Default")
      (node (ref "BK1") (pin "1") (pinfunction "VDDVCO_1") (pintype "passive"))
      (node (ref "C6") (pin "2") (pinfunction "2_2") (pintype "passive"))
    )
    (net (code "38") (name "Net-(BK1-XI)") (class "Default")
      (node (ref "BK1") (pin "31") (pinfunction "XI_31") (pintype "passive"))
      (node (ref "C19") (pin "1") (pinfunction "1_1") (pintype "passive"))
      (node (ref "Y1") (pin "1") (pinfunction "OSC1_1") (pintype "passive"))
    )
    (net (code "39") (name "Net-(BK1-XO)") (class "Default")
      (node (ref "BK1") (pin "30") (pinfunction "XO_30") (pintype "passive"))
      (node (ref "C20") (pin "1") (pinfunction "1_1") (pintype "passive"))
      (node (ref "Y1") (pin "2") (pinfunction "OSC2_2") (pintype "passive"))
    )
    (net (code "40") (name "Net-(C1-Pad2)") (class "Default")
      (node (ref "C1") (pin "2") (pinfunction "2_2") (pintype "passive"))
      (node (ref "C2") (pin "2") (pinfunction "2_2") (pintype "passive"))
      (node (ref "FB1") (pin "1") (pinfunction "1_1") (pintype "passive"))
      (node (ref "L1") (pin "2") (pinfunction "2_2") (pintype "passive"))
      (node (ref "L2") (pin "2") (pinfunction "2_2") (pintype "passive"))
    )
    (net (code "41") (name "Net-(C7-Pad2)") (class "Default")
      (node (ref "C7") (pin "2") (pinfunction "2_2") (pintype "passive"))
      (node (ref "C9") (pin "2") (pinfunction "2_2") (pintype "passive"))
      (node (ref "L4") (pin "2") (pinfunction "2_2") (pintype "passive"))
    )
    (net (code "42") (name "Net-(C14-Pad1)") (class "Default")
      (node (ref "C14") (pin "1") (pinfunction "1_1") (pintype "passive"))
      (node (ref "C15") (pin "2") (pinfunction "2_2") (pintype "passive"))
      (node (ref "L5") (pin "2") (pinfunction "2_2") (pintype "passive"))
    )
    (net (code "43") (name "Net-(C14-Pad2)") (class "Default")
      (node (ref "C14") (pin "2") (pinfunction "2_2") (pintype "passive"))
      (node (ref "C8") (pin "1") (pinfunction "1_1") (pintype "passive"))
      (node (ref "L4") (pin "1") (pinfunction "1_1") (pintype "passive"))
    )
    (net (code "44") (name "Net-(C17-Pad1)") (class "Default")
      (node (ref "C17") (pin "1") (pinfunction "1_1") (pintype "passive"))
      (node (ref "C8") (pin "2") (pinfunction "2_2") (pintype "passive"))
      (node (ref "L3") (pin "2") (pinfunction "2_2") (pintype "passive"))
    )
    (net (code "45") (name "Net-(D1-K)") (class "Default")
      (node (ref "D1") (pin "2") (pinfunction "K_2") (pintype "passive"))
      (node (ref "Q1") (pin "3") (pinfunction "C_3") (pintype "passive"))
      (node (ref "R8") (pin "2") (pinfunction "2_2") (pintype "passive"))
    )
    (net (code "46") (name "Net-(IC1-SCL)") (class "Default")
      (node (ref "IC1") (pin "6") (pinfunction "SCL_6") (pintype "input"))
      (node (ref "R23") (pin "1") (pinfunction "1_1") (pintype "passive"))
      (node (ref "U3") (pin "18") (pinfunction "I2C_SCL_18") (pintype "passive"))
    )
    (net (code "47") (name "Net-(IC1-SDA)") (class "Default")
      (node (ref "IC1") (pin "5") (pinfunction "SDA_5") (pintype "bidirectional"))
      (node (ref "R24") (pin "1") (pinfunction "1_1") (pintype "passive"))
      (node (ref "U3") (pin "19") (pinfunction "I2C_SDA_19") (pintype "passive"))
    )
    (net (code "48") (name "Net-(LED1-A)") (class "Default")
      (node (ref "LED1") (pin "1") (pinfunction "A_1") (pintype "passive"))
      (node (ref "R2") (pin "1") (pinfunction "1_1") (pintype "passive"))
    )
    (net (code "49") (name "Net-(LED2-A)") (class "Default")
      (node (ref "LED2") (pin "1") (pinfunction "A_1") (pintype "passive"))
      (node (ref "R22") (pin "1") (pinfunction "1_1") (pintype "passive"))
    )
    (net (code "50") (name "Net-(LED3-A)") (class "Default")
      (node (ref "LED3") (pin "1") (pinfunction "A_1") (pintype "passive"))
      (node (ref "R28") (pin "1") (pinfunction "1_1") (pintype "passive"))
    )
    (net (code "51") (name "Net-(LED4-A)") (class "Default")
      (node (ref "LED4") (pin "1") (pinfunction "A_1") (pintype "passive"))
      (node (ref "R31") (pin "1") (pinfunction "1_1") (pintype "passive"))
    )
    (net (code "52") (name "Net-(LED4-K)") (class "Default")
      (node (ref "LED4") (pin "2") (pinfunction "K_2") (pintype "passive"))
      (node (ref "Q3") (pin "3") (pinfunction "D_3") (pintype "passive"))
    )
    (net (code "53") (name "Net-(Q1-B)") (class "Default")
      (node (ref "Q1") (pin "1") (pinfunction "B_1") (pintype "passive"))
      (node (ref "R9") (pin "2") (pinfunction "2_2") (pintype "passive"))
    )
    (net (code "54") (name "Net-(Q2-B)") (class "Default")
      (node (ref "Q2") (pin "1") (pinfunction "B_1") (pintype "passive"))
      (node (ref "R10") (pin "2") (pinfunction "2_2") (pintype "passive"))
    )
    (net (code "55") (name "Net-(Q2-C)") (class "Default")
      (node (ref "Q2") (pin "3") (pinfunction "C_3") (pintype "passive"))
      (node (ref "R11") (pin "1") (pinfunction "1_1") (pintype "passive"))
    )
    (net (code "56") (name "Net-(Q3-G)") (class "Default")
      (node (ref "Q3") (pin "1") (pinfunction "G_1") (pintype "passive"))
      (node (ref "R29") (pin "1") (pinfunction "1_1") (pintype "passive"))
      (node (ref "R30") (pin "2") (pinfunction "2_2") (pintype "passive"))
    )
    (net (code "57") (name "Net-(U1A-PA3)") (class "Default")
      (node (ref "R29") (pin "2") (pinfunction "2_2") (pintype "passive"))
      (node (ref "U1") (pin "13") (pinfunction "PA3_13") (pintype "bidirectional"))
    )
    (net (code "58") (name "Net-(U1A-PB0)") (class "Default")
      (node (ref "C3") (pin "2") (pinfunction "2_2") (pintype "passive"))
      (node (ref "SW1") (pin "1") (pinfunction "1_1") (pintype "passive"))
      (node (ref "U1") (pin "18") (pinfunction "PB0_18") (pintype "bidirectional"))
    )
    (net (code "59") (name "Net-(U1A-PB1)") (class "Default")
      (node (ref "C55") (pin "2") (pinfunction "2_2") (pintype "passive"))
      (node (ref "SW3") (pin "1") (pinfunction "1_1") (pintype "passive"))
      (node (ref "U1") (pin "19") (pinfunction "PB1_19") (pintype "bidirectional"))
    )
    (net (code "60") (name "Net-(U1A-PB2)") (class "Default")
      (node (ref "R3") (pin "1") (pinfunction "1_1") (pintype "passive"))
      (node (ref "U1") (pin "20") (pinfunction "PB2_20") (pintype "bidirectional"))
    )
    (net (code "61") (name "Net-(U1A-PD0-OSC_IN)") (class "Default")
      (node (ref "C26") (pin "2") (pinfunction "2_2") (pintype "passive"))
      (node (ref "U1") (pin "5") (pinfunction "PD0-OSC_IN_5") (pintype "bidirectional"))
      (node (ref "Y2") (pin "2") (pinfunction "OSC2_2") (pintype "passive"))
    )
    (net (code "62") (name "Net-(U1A-PD1)") (class "Default")
      (node (ref "C27") (pin "2") (pinfunction "2_2") (pintype "passive"))
      (node (ref "U1") (pin "6") (pinfunction "PD1_6") (pintype "bidirectional"))
      (node (ref "Y2") (pin "1") (pinfunction "OSC1_1") (pintype "passive"))
    )
    (net (code "63") (name "Net-(U2-EN)") (class "Default")
      (node (ref "R33") (pin "1") (pinfunction "1_1") (pintype "passive"))
      (node (ref "U2") (pin "3") (pinfunction "EN_3") (pintype "passive"))
    )
    (net (code "64") (name "Net-(U3-CFLYN)") (class "Default")
      (node (ref "C38") (pin "1") (pinfunction "1_1") (pintype "passive"))
      (node (ref "U3") (pin "43") (pinfunction "CFLYN_43") (pintype "passive"))
    )
    (net (code "65") (name "Net-(U3-CFLYP)") (class "Default")
      (node (ref "C38") (pin "2") (pinfunction "2_2") (pintype "passive"))
      (node (ref "U3") (pin "45") (pinfunction "CFLYP_45") (pintype "passive"))
    )
    (net (code "66") (name "Net-(U3-HPVDD)") (class "Default")
      (node (ref "C42") (pin "2") (pinfunction "2_2") (pintype "passive"))
      (node (ref "U3") (pin "40") (pinfunction "HPVDD_40") (pintype "passive"))
      (node (ref "U3") (pin "41") (pinfunction "VCPP_41") (pintype "passive"))
    )
    (net (code "67") (name "Net-(U3-HPVSS)") (class "Default")
      (node (ref "C40") (pin "2") (pinfunction "2_2") (pintype "passive"))
      (node (ref "U3") (pin "37") (pinfunction "HPVSS_37") (pintype "passive"))
      (node (ref "U3") (pin "42") (pinfunction "VCPN_42") (pintype "passive"))
    )
    (net (code "68") (name "Net-(U3-INSEL)") (class "Default")
      (node (ref "R27") (pin "1") (pinfunction "1_1") (pintype "passive"))
      (node (ref "U3") (pin "9") (pinfunction "INSEL_9") (pintype "passive"))
    )
    (net (code "69") (name "Net-(U3-KEY_RENC_INV)") (class "Default")
      (node (ref "R15") (pin "1") (pinfunction "1_1") (pintype "passive"))
      (node (ref "U3") (pin "7") (pinfunction "KEY_RENC_INV_7") (pintype "passive"))
    )
    (net (code "70") (name "Net-(U3-LEDO)") (class "Default")
      (node (ref "R22") (pin "2") (pinfunction "2_2") (pintype "passive"))
      (node (ref "U3") (pin "8") (pinfunction "LEDO_8") (pintype "passive"))
    )
    (net (code "71") (name "Net-(U3-STEREO_MIC)") (class "Default")
      (node (ref "R17") (pin "1") (pinfunction "1_1") (pintype "passive"))
      (node (ref "U3") (pin "13") (pinfunction "STEREO_MIC_13") (pintype "passive"))
    )
    (net (code "72") (name "Net-(U3-TEST)") (class "Default")
      (node (ref "R14") (pin "1") (pinfunction "1_1") (pintype "passive"))
      (node (ref "U3") (pin "47") (pinfunction "TEST_47") (pintype "passive"))
    )
    (net (code "73") (name "Net-(U3-V12)") (class "Default")
      (node (ref "C41") (pin "2") (pinfunction "2_2") (pintype "passive"))
      (node (ref "U3") (pin "4") (pinfunction "V12_4") (pintype "passive"))
    )
    (net (code "74") (name "Net-(U3-VMID)") (class "Default")
      (node (ref "C43") (pin "2") (pinfunction "2_2") (pintype "passive"))
      (node (ref "C44") (pin "2") (pinfunction "2_2") (pintype "passive"))
      (node (ref "U3") (pin "35") (pinfunction "VMID_35") (pintype "passive"))
    )
    (net (code "75") (name "Net-(USBC1-CC1)") (class "Default")
      (node (ref "R25") (pin "2") (pinfunction "2_2") (pintype "passive"))
      (node (ref "USBC1") (pin "A5") (pinfunction "CC1_A5") (pintype "passive"))
    )
    (net (code "76") (name "Net-(USBC1-CC2)") (class "Default")
      (node (ref "R26") (pin "1") (pinfunction "1_1") (pintype "passive"))
      (node (ref "USBC1") (pin "B5") (pinfunction "CC2_B5") (pintype "passive"))
    )
    (net (code "77") (name "RF3V3") (class "Default")
      (node (ref "BK1") (pin "13") (pinfunction "VCCAUD_13") (pintype "passive"))
      (node (ref "BK1") (pin "16") (pinfunction "VCCDIG_16") (pintype "passive"))
      (node (ref "BK1") (pin "2") (pinfunction "VCCVCO_2") (pintype "passive"))
      (node (ref "BK1") (pin "24") (pinfunction "VCCIF_24") (pintype "passive"))
      (node (ref "BK1") (pin "28") (pinfunction "VCCDVCO_28") (pintype "passive"))
      (node (ref "BK1") (pin "29") (pinfunction "VCCXTAL_29") (pintype "passive"))
      (node (ref "BK1") (pin "32") (pinfunction "VCCPLL_32") (pintype "passive"))
      (node (ref "BK1") (pin "4") (pinfunction "VCCB_4") (pintype "passive"))
      (node (ref "BK1") (pin "8") (pinfunction "VCCPA_8") (pintype "passive"))
      (node (ref "C18") (pin "1") (pinfunction "1_1") (pintype "passive"))
      (node (ref "C22") (pin "2") (pinfunction "2_2") (pintype "passive"))
      (node (ref "C25") (pin "1") (pinfunction "1_1") (pintype "passive"))
      (node (ref "C30") (pin "2") (pinfunction "2_2") (pintype "passive"))
      (node (ref "C32") (pin "2") (pinfunction "2_2") (pintype "passive"))
      (node (ref "C4") (pin "2") (pinfunction "2_2") (pintype "passive"))
      (node (ref "C5") (pin "2") (pinfunction "2_2") (pintype "passive"))
      (node (ref "C53") (pin "1") (pinfunction "1_1") (pintype "passive"))
      (node (ref "U4") (pin "5") (pinfunction "VOUT_5") (pintype "passive"))
    )
    (net (code "78") (name "USB_5V") (class "Default")
      (node (ref "C23") (pin "1") (pinfunction "1_1") (pintype "passive"))
      (node (ref "C49") (pin "2") (pinfunction "2_2") (pintype "passive"))
      (node (ref "C52") (pin "1") (pinfunction "1_1") (pintype "passive"))
      (node (ref "C54") (pin "1") (pinfunction "1_1") (pintype "passive"))
      (node (ref "FB5") (pin "1") (pinfunction "1_1") (pintype "passive"))
      (node (ref "R33") (pin "2") (pinfunction "2_2") (pintype "passive"))
      (node (ref "U2") (pin "1") (pinfunction "VIN_1") (pintype "passive"))
      (node (ref "U4") (pin "1") (pinfunction "VIN_1") (pintype "passive"))
    )
    (net (code "79") (name "VBUS") (class "Default")
      (node (ref "C50") (pin "2") (pinfunction "2_2") (pintype "passive"))
      (node (ref "C51") (pin "2") (pinfunction "2_2") (pintype "passive"))
      (node (ref "FB5") (pin "2") (pinfunction "2_2") (pintype "passive"))
      (node (ref "U3") (pin "1") (pinfunction "VBUS_1") (pintype "passive"))
      (node (ref "USBC1") (pin "A4") (pinfunction "VBUS_A4") (pintype "passive"))
      (node (ref "USBC1") (pin "A9") (pinfunction "VBUS_A9") (pintype "passive"))
      (node (ref "USBC1") (pin "B4") (pinfunction "VBUS_B4") (pintype "passive"))
      (node (ref "USBC1") (pin "B9") (pinfunction "VBUS_B9") (pintype "passive"))
    )
    (net (code "80") (name "VDDA") (class "Default")
      (node (ref "C12") (pin "2") (pinfunction "2_2") (pintype "passive"))
      (node (ref "C13") (pin "2") (pinfunction "2_2") (pintype "passive"))
      (node (ref "FB2") (pin "2") (pinfunction "2_2") (pintype "passive"))
      (node (ref "U1") (pin "9") (pinfunction "VDDA_9") (pintype "power_in"))
    )
    (net (code "81") (name "VSSA") (class "Default")
      (node (ref "C12") (pin "1") (pinfunction "1_1") (pintype "passive"))
      (node (ref "C13") (pin "1") (pinfunction "1_1") (pintype "passive"))
      (node (ref "FB3") (pin "2") (pinfunction "2_2") (pintype "passive"))
      (node (ref "U1") (pin "8") (pinfunction "VSSA_8") (pintype "power_in"))
    )
    (net (code "82") (name "unconnected-(BK1-GPIO2-Pad20)") (class "Default")
      (node (ref "BK1") (pin "20") (pinfunction "GPIO2_20") (pintype "passive"))
    )
    (net (code "83") (name "unconnected-(BK1-GPIO4-Pad25)") (class "Default")
      (node (ref "BK1") (pin "25") (pinfunction "GPIO4_25") (pintype "passive+no_connect"))
    )
    (net (code "84") (name "unconnected-(BK1-IRQ-Pad27)") (class "Default")
      (node (ref "BK1") (pin "27") (pinfunction "IRQ_27") (pintype "passive+no_connect"))
    )
    (net (code "85") (name "unconnected-(BK1-MICN-Pad14)") (class "Default")
      (node (ref "BK1") (pin "14") (pinfunction "MICN_14") (pintype "passive+no_connect"))
    )
    (net (code "86") (name "unconnected-(BK1-MICP-Pad15)") (class "Default")
      (node (ref "BK1") (pin "15") (pinfunction "MICP_15") (pintype "passive+no_connect"))
    )
    (net (code "87") (name "unconnected-(BK1-NC-Pad5)") (class "Default")
      (node (ref "BK1") (pin "5") (pinfunction "NC_5") (pintype "passive"))
    )
    (net (code "88") (name "unconnected-(BK1-NC-Pad6)") (class "Default")
      (node (ref "BK1") (pin "6") (pinfunction "NC_6") (pintype "passive"))
    )
    (net (code "89") (name "unconnected-(IC1-WP-Pad7)") (class "Default")
      (node (ref "IC1") (pin "7") (pinfunction "WP_7") (pintype "passive+no_connect"))
    )
    (net (code "90") (name "unconnected-(U1A-PA0-WKUP-Pad10)") (class "Default")
      (node (ref "U1") (pin "10") (pinfunction "PA0-WKUP_10") (pintype "bidirectional"))
    )
    (net (code "91") (name "unconnected-(U1A-PA1-Pad11)") (class "Default")
      (node (ref "U1") (pin "11") (pinfunction "PA1_11") (pintype "bidirectional"))
    )
    (net (code "92") (name "unconnected-(U1A-PA2-Pad12)") (class "Default")
      (node (ref "U1") (pin "12") (pinfunction "PA2_12") (pintype "bidirectional"))
    )
    (net (code "93") (name "unconnected-(U1A-PA4-Pad14)") (class "Default")
      (node (ref "U1") (pin "14") (pinfunction "PA4_14") (pintype "bidirectional"))
    )
    (net (code "94") (name "unconnected-(U1A-PA8-Pad29)") (class "Default")
      (node (ref "U1") (pin "29") (pinfunction "PA8_29") (pintype "bidirectional"))
    )
    (net (code "95") (name "unconnected-(U1A-PA11-Pad32)") (class "Default")
      (node (ref "U1") (pin "32") (pinfunction "PA11_32") (pintype "bidirectional"))
    )
    (net (code "96") (name "unconnected-(U1A-PA12-Pad33)") (class "Default")
      (node (ref "U1") (pin "33") (pinfunction "PA12_33") (pintype "bidirectional"))
    )
    (net (code "97") (name "unconnected-(U1A-PA15-Pad38)") (class "Default")
      (node (ref "U1") (pin "38") (pinfunction "PA15_38") (pintype "bidirectional"))
    )
    (net (code "98") (name "unconnected-(U1A-PB3-Pad39)") (class "Default")
      (node (ref "U1") (pin "39") (pinfunction "PB3_39") (pintype "bidirectional"))
    )
    (net (code "99") (name "unconnected-(U1A-PB5-Pad41)") (class "Default")
      (node (ref "U1") (pin "41") (pinfunction "PB5_41") (pintype "bidirectional"))
    )
    (net (code "100") (name "unconnected-(U1A-PB8-Pad45)") (class "Default")
      (node (ref "U1") (pin "45") (pinfunction "PB8_45") (pintype "bidirectional"))
    )
    (net (code "101") (name "unconnected-(U1A-PB9-Pad46)") (class "Default")
      (node (ref "U1") (pin "46") (pinfunction "PB9_46") (pintype "bidirectional"))
    )
    (net (code "102") (name "unconnected-(U1A-PB10-Pad21)") (class "Default")
      (node (ref "U1") (pin "21") (pinfunction "PB10_21") (pintype "bidirectional"))
    )
    (net (code "103") (name "unconnected-(U1A-PB11-Pad22)") (class "Default")
      (node (ref "U1") (pin "22") (pinfunction "PB11_22") (pintype "bidirectional"))
    )
    (net (code "104") (name "unconnected-(U1A-PB12-Pad25)") (class "Default")
      (node (ref "U1") (pin "25") (pinfunction "PB12_25") (pintype "bidirectional"))
    )
    (net (code "105") (name "unconnected-(U1A-PB14-Pad27)") (class "Default")
      (node (ref "U1") (pin "27") (pinfunction "PB14_27") (pintype "bidirectional"))
    )
    (net (code "106") (name "unconnected-(U1A-PB15-Pad28)") (class "Default")
      (node (ref "U1") (pin "28") (pinfunction "PB15_28") (pintype "bidirectional"))
    )
    (net (code "107") (name "unconnected-(U1A-PC13-TAMPER-RTC-Pad2)") (class "Default")
      (node (ref "U1") (pin "2") (pinfunction "PC13-TAMPER-RTC_2") (pintype "bidirectional"))
    )
    (net (code "108") (name "unconnected-(U1A-PC14-OSC32_IN-Pad3)") (class "Default")
      (node (ref "U1") (pin "3") (pinfunction "PC14-OSC32_IN_3") (pintype "bidirectional"))
    )
    (net (code "109") (name "unconnected-(U1A-PC15-OSC32_OUT-Pad4)") (class "Default")
      (node (ref "U1") (pin "4") (pinfunction "PC15-OSC32_OUT_4") (pintype "bidirectional"))
    )
    (net (code "110") (name "unconnected-(U2-NC-Pad4)") (class "Default")
      (node (ref "U2") (pin "4") (pinfunction "NC_4") (pintype "passive+no_connect"))
    )
    (net (code "111") (name "unconnected-(U3-EQ3D_LED-Pad48)") (class "Default")
      (node (ref "U3") (pin "48") (pinfunction "EQ3D_LED_48") (pintype "passive+no_connect"))
    )
    (net (code "112") (name "unconnected-(U3-LHPOUT-Pad39)") (class "Default")
      (node (ref "U3") (pin "39") (pinfunction "LHPOUT_39") (pintype "passive+no_connect"))
    )
    (net (code "113") (name "unconnected-(U3-MIC1-Pad29)") (class "Default")
      (node (ref "U3") (pin "29") (pinfunction "MIC1_29") (pintype "passive+no_connect"))
    )
    (net (code "114") (name "unconnected-(U3-MIC1N-Pad31)") (class "Default")
      (node (ref "U3") (pin "31") (pinfunction "MIC1N_31") (pintype "passive+no_connect"))
    )
    (net (code "115") (name "unconnected-(U3-MIC1P-Pad32)") (class "Default")
      (node (ref "U3") (pin "32") (pinfunction "MIC1P_32") (pintype "passive+no_connect"))
    )
    (net (code "116") (name "unconnected-(U3-MIC2P-Pad33)") (class "Default")
      (node (ref "U3") (pin "33") (pinfunction "MIC2P_33") (pintype "passive+no_connect"))
    )
    (net (code "117") (name "unconnected-(U3-MICBIAS-Pad30)") (class "Default")
      (node (ref "U3") (pin "30") (pinfunction "MICBIAS_30") (pintype "passive+no_connect"))
    )
    (net (code "118") (name "unconnected-(U3-MSEL-Pad10)") (class "Default")
      (node (ref "U3") (pin "10") (pinfunction "MSEL_10") (pintype "passive+no_connect"))
    )
    (net (code "119") (name "unconnected-(U3-NEXT_TRACK-Pad20)") (class "Default")
      (node (ref "U3") (pin "20") (pinfunction "NEXT_TRACK_20") (pintype "passive+no_connect"))
    )
    (net (code "120") (name "unconnected-(U3-PALY_PAUSE-Pad22)") (class "Default")
      (node (ref "U3") (pin "22") (pinfunction "PALY_PAUSE_22") (pintype "passive+no_connect"))
    )
    (net (code "121") (name "unconnected-(U3-PLAY_EN-Pad16)") (class "Default")
      (node (ref "U3") (pin "16") (pinfunction "PLAY_EN_16") (pintype "passive+no_connect"))
    )
    (net (code "122") (name "unconnected-(U3-PRE_TACK-Pad21)") (class "Default")
      (node (ref "U3") (pin "21") (pinfunction "PRE_TACK_21") (pintype "passive+no_connect"))
    )
    (net (code "123") (name "unconnected-(U3-REC_EN-Pad17)") (class "Default")
      (node (ref "U3") (pin "17") (pinfunction "REC_EN_17") (pintype "passive+no_connect"))
    )
    (net (code "124") (name "unconnected-(U3-RHPOUT-Pad38)") (class "Default")
      (node (ref "U3") (pin "38") (pinfunction "RHPOUT_38") (pintype "passive+no_connect"))
    )
    (net (code "125") (name "unconnected-(U3-RING2-Pad28)") (class "Default")
      (node (ref "U3") (pin "28") (pinfunction "RING2_28") (pintype "passive+no_connect"))
    )
    (net (code "126") (name "unconnected-(U3-SLEEVE-Pad26)") (class "Default")
      (node (ref "U3") (pin "26") (pinfunction "SLEEVE_26") (pintype "passive+no_connect"))
    )
    (net (code "127") (name "unconnected-(U3-STOP-Pad24)") (class "Default")
      (node (ref "U3") (pin "24") (pinfunction "STOP_24") (pintype "passive+no_connect"))
    )
    (net (code "128") (name "unconnected-(U3-VOLDN-Pad15)") (class "Default")
      (node (ref "U3") (pin "15") (pinfunction "VOLDN_15") (pintype "passive+no_connect"))
    )
    (net (code "129") (name "unconnected-(U3-VP_MUTE-Pad25)") (class "Default")
      (node (ref "U3") (pin "25") (pinfunction "VP_MUTE_25") (pintype "passive+no_connect"))
    )
    (net (code "130") (name "unconnected-(U3-VR_MUTE-Pad23)") (class "Default")
      (node (ref "U3") (pin "23") (pinfunction "VR_MUTE_23") (pintype "passive+no_connect"))
    )
    (net (code "131") (name "unconnected-(U4-NC-Pad4)") (class "Default")
      (node (ref "U4") (pin "4") (pinfunction "NC_4") (pintype "passive+no_connect"))
    )
    (net (code "132") (name "unconnected-(USBC1-SBU1-PadA8)") (class "Default")
      (node (ref "USBC1") (pin "A8") (pinfunction "SBU1_A8") (pintype "passive"))
    )
    (net (code "133") (name "unconnected-(USBC1-SBU2-PadB8)") (class "Default")
      (node (ref "USBC1") (pin "B8") (pinfunction "SBU2_B8") (pintype "passive"))
    )
  )
)
